# shield.net
KiCad netlist of a schematic drawn in EAGLE
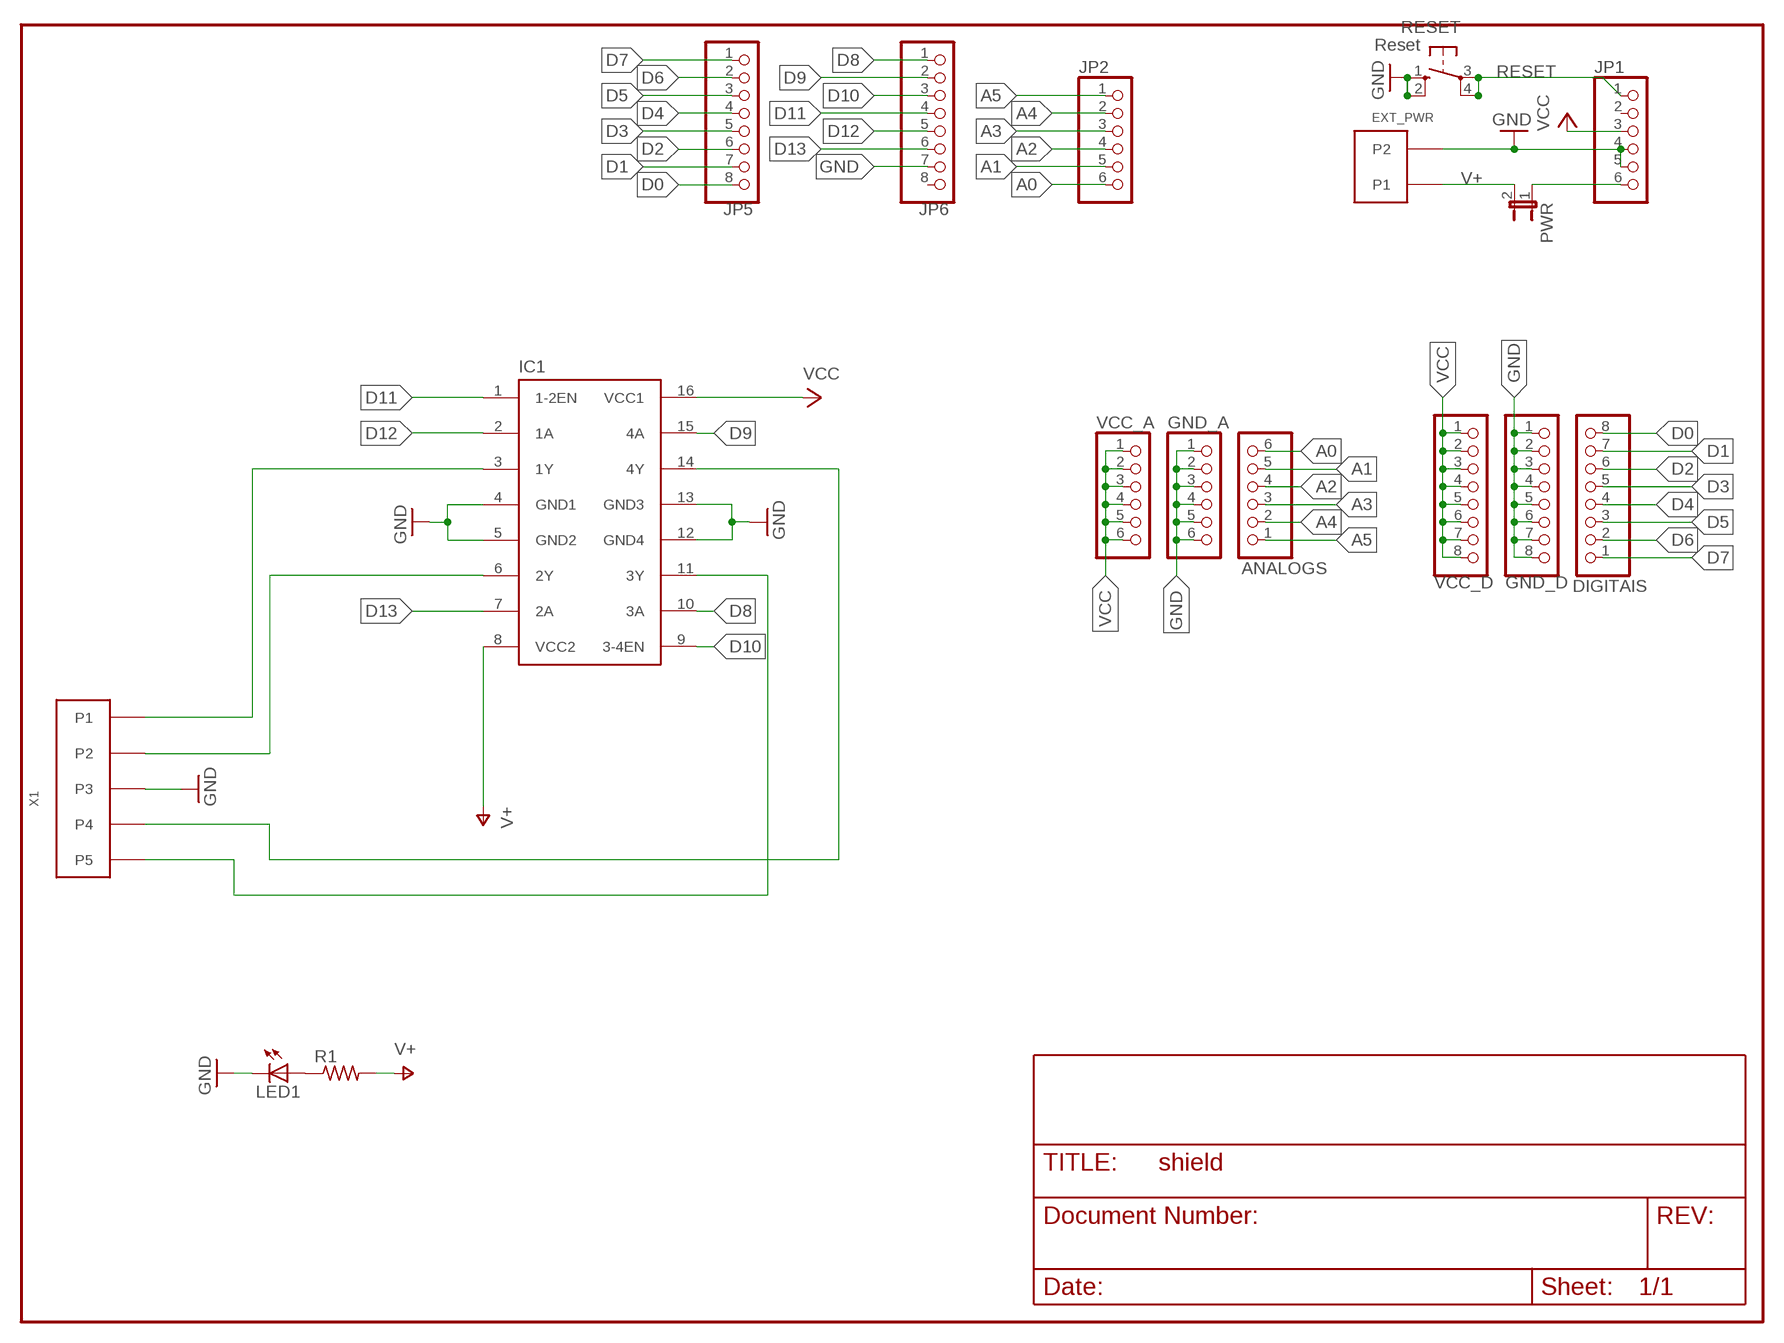
[diagram p0: schematic, sheet 1]

(export (version "E")
  (design (tool "Eeschema 10.0.6"))
  (components
    (comp (ref "ANALOGS")
      (value "PINHD-1X6")
      (footprint "eagle-import:1X06")
      (libsource (lib "eagle-import") (part "PINHD-1X6"))
    )
    (comp (ref "DIGITAIS")
      (value "PINHD-1X8")
      (footprint "eagle-import:1X08")
      (libsource (lib "eagle-import") (part "PINHD-1X8"))
    )
    (comp (ref "EXT_PWR")
      (value "PINHEAD")
      (footprint "eagle-import:TERMBLOCK508")
      (libsource (lib "eagle-import") (part "PINHEAD"))
    )
    (comp (ref "GND_A")
      (value "PINHD-1X6")
      (footprint "eagle-import:1X06")
      (libsource (lib "eagle-import") (part "PINHD-1X6"))
    )
    (comp (ref "GND_D")
      (value "PINHD-1X8")
      (footprint "eagle-import:1X08")
      (libsource (lib "eagle-import") (part "PINHD-1X8"))
    )
    (comp (ref "IC1")
      (value "L293E")
      (footprint "eagle-import:DIL16")
      (libsource (lib "eagle-import") (part "L293E"))
    )
    (comp (ref "JP1")
      (value "PINHD-1X6")
      (footprint "eagle-import:1X06")
      (libsource (lib "eagle-import") (part "PINHD-1X6"))
    )
    (comp (ref "JP2")
      (value "PINHD-1X6")
      (footprint "eagle-import:1X06")
      (libsource (lib "eagle-import") (part "PINHD-1X6"))
    )
    (comp (ref "JP5")
      (value "PINHD-1X8")
      (footprint "eagle-import:1X08")
      (libsource (lib "eagle-import") (part "PINHD-1X8"))
    )
    (comp (ref "JP6")
      (value "PINHD-1X8")
      (footprint "eagle-import:1X08")
      (libsource (lib "eagle-import") (part "PINHD-1X8"))
    )
    (comp (ref "LED1")
      (value "LED3MM")
      (footprint "eagle-import:LED3MM")
      (libsource (lib "eagle-import") (part "LED3MM"))
    )
    (comp (ref "PWR")
      (value "JP1E")
      (footprint "eagle-import:JP1")
      (libsource (lib "eagle-import") (part "JP1E"))
    )
    (comp (ref "R1")
      (value "R-US_0207/10")
      (footprint "eagle-import:0207_10")
      (libsource (lib "eagle-import") (part "R-US_0207/10"))
    )
    (comp (ref "RESET")
      (value "Reset")
      (footprint "eagle-import:B3F-10XX")
      (libsource (lib "eagle-import") (part "10-XX"))
    )
    (comp (ref "VCC_A")
      (value "PINHD-1X6")
      (footprint "eagle-import:1X06")
      (libsource (lib "eagle-import") (part "PINHD-1X6"))
    )
    (comp (ref "VCC_D")
      (value "PINHD-1X8")
      (footprint "eagle-import:1X08")
      (libsource (lib "eagle-import") (part "PINHD-1X8"))
    )
    (comp (ref "X1")
      (value "TERM5")
      (footprint "eagle-import:TERM1X5")
      (libsource (lib "eagle-import") (part "TERM5"))
    )
  )
  (nets
    (net (code "1") (name "/RESET") (class "Default")
      (node (ref "JP1") (pin "1") (pinfunction "1_1") (pintype "passive"))
      (node (ref "RESET") (pin "3") (pinfunction "P_3") (pintype "passive"))
      (node (ref "RESET") (pin "4") (pinfunction "P1_4") (pintype "passive"))
    )
    (net (code "2") (name "A0") (class "Default")
      (node (ref "ANALOGS") (pin "6") (pinfunction "6_6") (pintype "passive"))
      (node (ref "JP2") (pin "6") (pinfunction "6_6") (pintype "passive"))
    )
    (net (code "3") (name "A1") (class "Default")
      (node (ref "ANALOGS") (pin "5") (pinfunction "5_5") (pintype "passive"))
      (node (ref "JP2") (pin "5") (pinfunction "5_5") (pintype "passive"))
    )
    (net (code "4") (name "A2") (class "Default")
      (node (ref "ANALOGS") (pin "4") (pinfunction "4_4") (pintype "passive"))
      (node (ref "JP2") (pin "4") (pinfunction "4_4") (pintype "passive"))
    )
    (net (code "5") (name "A3") (class "Default")
      (node (ref "ANALOGS") (pin "3") (pinfunction "3_3") (pintype "passive"))
      (node (ref "JP2") (pin "3") (pinfunction "3_3") (pintype "passive"))
    )
    (net (code "6") (name "A4") (class "Default")
      (node (ref "ANALOGS") (pin "2") (pinfunction "2_2") (pintype "passive"))
      (node (ref "JP2") (pin "2") (pinfunction "2_2") (pintype "passive"))
    )
    (net (code "7") (name "A5") (class "Default")
      (node (ref "ANALOGS") (pin "1") (pinfunction "1_1") (pintype "passive"))
      (node (ref "JP2") (pin "1") (pinfunction "1_1") (pintype "passive"))
    )
    (net (code "8") (name "D0") (class "Default")
      (node (ref "DIGITAIS") (pin "8") (pinfunction "8_8") (pintype "passive"))
      (node (ref "JP5") (pin "8") (pinfunction "8_8") (pintype "passive"))
    )
    (net (code "9") (name "D1") (class "Default")
      (node (ref "DIGITAIS") (pin "7") (pinfunction "7_7") (pintype "passive"))
      (node (ref "JP5") (pin "7") (pinfunction "7_7") (pintype "passive"))
    )
    (net (code "10") (name "D2") (class "Default")
      (node (ref "DIGITAIS") (pin "6") (pinfunction "6_6") (pintype "passive"))
      (node (ref "JP5") (pin "6") (pinfunction "6_6") (pintype "passive"))
    )
    (net (code "11") (name "D3") (class "Default")
      (node (ref "DIGITAIS") (pin "5") (pinfunction "5_5") (pintype "passive"))
      (node (ref "JP5") (pin "5") (pinfunction "5_5") (pintype "passive"))
    )
    (net (code "12") (name "D4") (class "Default")
      (node (ref "DIGITAIS") (pin "4") (pinfunction "4_4") (pintype "passive"))
      (node (ref "JP5") (pin "4") (pinfunction "4_4") (pintype "passive"))
    )
    (net (code "13") (name "D5") (class "Default")
      (node (ref "DIGITAIS") (pin "3") (pinfunction "3_3") (pintype "passive"))
      (node (ref "JP5") (pin "3") (pinfunction "3_3") (pintype "passive"))
    )
    (net (code "14") (name "D6") (class "Default")
      (node (ref "DIGITAIS") (pin "2") (pinfunction "2_2") (pintype "passive"))
      (node (ref "JP5") (pin "2") (pinfunction "2_2") (pintype "passive"))
    )
    (net (code "15") (name "D7") (class "Default")
      (node (ref "DIGITAIS") (pin "1") (pinfunction "1_1") (pintype "passive"))
      (node (ref "JP5") (pin "1") (pinfunction "1_1") (pintype "passive"))
    )
    (net (code "16") (name "D8") (class "Default")
      (node (ref "IC1") (pin "10") (pinfunction "3A_10") (pintype "input"))
      (node (ref "JP6") (pin "1") (pinfunction "1_1") (pintype "passive"))
    )
    (net (code "17") (name "D9") (class "Default")
      (node (ref "IC1") (pin "15") (pinfunction "4A_15") (pintype "input"))
      (node (ref "JP6") (pin "2") (pinfunction "2_2") (pintype "passive"))
    )
    (net (code "18") (name "D10") (class "Default")
      (node (ref "IC1") (pin "9") (pinfunction "3-4EN_9") (pintype "input"))
      (node (ref "JP6") (pin "3") (pinfunction "3_3") (pintype "passive"))
    )
    (net (code "19") (name "D11") (class "Default")
      (node (ref "IC1") (pin "1") (pinfunction "1-2EN_1") (pintype "input"))
      (node (ref "JP6") (pin "4") (pinfunction "4_4") (pintype "passive"))
    )
    (net (code "20") (name "D12") (class "Default")
      (node (ref "IC1") (pin "2") (pinfunction "1A_2") (pintype "input"))
      (node (ref "JP6") (pin "5") (pinfunction "5_5") (pintype "passive"))
    )
    (net (code "21") (name "D13") (class "Default")
      (node (ref "IC1") (pin "7") (pinfunction "2A_7") (pintype "input"))
      (node (ref "JP6") (pin "6") (pinfunction "6_6") (pintype "passive"))
    )
    (net (code "22") (name "GND") (class "Default")
      (node (ref "EXT_PWR") (pin "P$4") (pinfunction "P2_P$4") (pintype "bidirectional"))
      (node (ref "GND_A") (pin "1") (pinfunction "1_1") (pintype "passive"))
      (node (ref "GND_A") (pin "2") (pinfunction "2_2") (pintype "passive"))
      (node (ref "GND_A") (pin "3") (pinfunction "3_3") (pintype "passive"))
      (node (ref "GND_A") (pin "4") (pinfunction "4_4") (pintype "passive"))
      (node (ref "GND_A") (pin "5") (pinfunction "5_5") (pintype "passive"))
      (node (ref "GND_A") (pin "6") (pinfunction "6_6") (pintype "passive"))
      (node (ref "GND_D") (pin "1") (pinfunction "1_1") (pintype "passive"))
      (node (ref "GND_D") (pin "2") (pinfunction "2_2") (pintype "passive"))
      (node (ref "GND_D") (pin "3") (pinfunction "3_3") (pintype "passive"))
      (node (ref "GND_D") (pin "4") (pinfunction "4_4") (pintype "passive"))
      (node (ref "GND_D") (pin "5") (pinfunction "5_5") (pintype "passive"))
      (node (ref "GND_D") (pin "6") (pinfunction "6_6") (pintype "passive"))
      (node (ref "GND_D") (pin "7") (pinfunction "7_7") (pintype "passive"))
      (node (ref "GND_D") (pin "8") (pinfunction "8_8") (pintype "passive"))
      (node (ref "IC1") (pin "12") (pinfunction "GND4_12") (pintype "power_in"))
      (node (ref "IC1") (pin "13") (pinfunction "GND3_13") (pintype "power_in"))
      (node (ref "IC1") (pin "4") (pinfunction "GND1_4") (pintype "power_in"))
      (node (ref "IC1") (pin "5") (pinfunction "GND2_5") (pintype "power_in"))
      (node (ref "JP1") (pin "4") (pinfunction "4_4") (pintype "passive"))
      (node (ref "JP1") (pin "5") (pinfunction "5_5") (pintype "passive"))
      (node (ref "JP6") (pin "7") (pinfunction "7_7") (pintype "passive"))
      (node (ref "LED1") (pin "K") (pinfunction "C_K") (pintype "passive"))
      (node (ref "RESET") (pin "1") (pinfunction "S_1") (pintype "passive"))
      (node (ref "RESET") (pin "2") (pinfunction "S1_2") (pintype "passive"))
      (node (ref "X1") (pin "P3") (pinfunction "P3_P3") (pintype "bidirectional"))
    )
    (net (code "23") (name "Net-(IC1-1Y)") (class "Default")
      (node (ref "IC1") (pin "3") (pinfunction "1Y_3") (pintype "output"))
      (node (ref "X1") (pin "P1") (pinfunction "P1_P1") (pintype "bidirectional"))
    )
    (net (code "24") (name "Net-(IC1-2Y)") (class "Default")
      (node (ref "IC1") (pin "6") (pinfunction "2Y_6") (pintype "output"))
      (node (ref "X1") (pin "P2") (pinfunction "P2_P2") (pintype "bidirectional"))
    )
    (net (code "25") (name "Net-(IC1-3Y)") (class "Default")
      (node (ref "IC1") (pin "11") (pinfunction "3Y_11") (pintype "output"))
      (node (ref "X1") (pin "P5") (pinfunction "P5_P5") (pintype "bidirectional"))
    )
    (net (code "26") (name "Net-(IC1-4Y)") (class "Default")
      (node (ref "IC1") (pin "14") (pinfunction "4Y_14") (pintype "output"))
      (node (ref "X1") (pin "P4") (pinfunction "P4_P4") (pintype "bidirectional"))
    )
    (net (code "27") (name "Net-(JP1-Pad6)") (class "Default")
      (node (ref "JP1") (pin "6") (pinfunction "6_6") (pintype "passive"))
      (node (ref "PWR") (pin "1") (pinfunction "1_1") (pintype "passive"))
    )
    (net (code "28") (name "Net-(LED1-PadA)") (class "Default")
      (node (ref "LED1") (pin "A") (pinfunction "A_A") (pintype "passive"))
      (node (ref "R1") (pin "1") (pinfunction "1_1") (pintype "passive"))
    )
    (net (code "29") (name "V+") (class "Default")
      (node (ref "EXT_PWR") (pin "P$3") (pinfunction "P1_P$3") (pintype "bidirectional"))
      (node (ref "IC1") (pin "8") (pinfunction "VCC2_8") (pintype "power_in"))
      (node (ref "PWR") (pin "2") (pinfunction "2_2") (pintype "passive"))
      (node (ref "R1") (pin "2") (pinfunction "2_2") (pintype "passive"))
    )
    (net (code "30") (name "VCC") (class "Default")
      (node (ref "IC1") (pin "16") (pinfunction "VCC1_16") (pintype "power_in"))
      (node (ref "JP1") (pin "3") (pinfunction "3_3") (pintype "passive"))
      (node (ref "VCC_A") (pin "1") (pinfunction "1_1") (pintype "passive"))
      (node (ref "VCC_A") (pin "2") (pinfunction "2_2") (pintype "passive"))
      (node (ref "VCC_A") (pin "3") (pinfunction "3_3") (pintype "passive"))
      (node (ref "VCC_A") (pin "4") (pinfunction "4_4") (pintype "passive"))
      (node (ref "VCC_A") (pin "5") (pinfunction "5_5") (pintype "passive"))
      (node (ref "VCC_A") (pin "6") (pinfunction "6_6") (pintype "passive"))
      (node (ref "VCC_D") (pin "1") (pinfunction "1_1") (pintype "passive"))
      (node (ref "VCC_D") (pin "2") (pinfunction "2_2") (pintype "passive"))
      (node (ref "VCC_D") (pin "3") (pinfunction "3_3") (pintype "passive"))
      (node (ref "VCC_D") (pin "4") (pinfunction "4_4") (pintype "passive"))
      (node (ref "VCC_D") (pin "5") (pinfunction "5_5") (pintype "passive"))
      (node (ref "VCC_D") (pin "6") (pinfunction "6_6") (pintype "passive"))
      (node (ref "VCC_D") (pin "7") (pinfunction "7_7") (pintype "passive"))
      (node (ref "VCC_D") (pin "8") (pinfunction "8_8") (pintype "passive"))
    )
    (net (code "31") (name "unconnected-(JP1-Pad2)") (class "Default")
      (node (ref "JP1") (pin "2") (pinfunction "2_2") (pintype "passive"))
    )
    (net (code "32") (name "unconnected-(JP6-Pad8)") (class "Default")
      (node (ref "JP6") (pin "8") (pinfunction "8_8") (pintype "passive"))
    )
  )
)
